# Qwiic-OpenLog.net
KiCad netlist of a schematic drawn in EAGLE
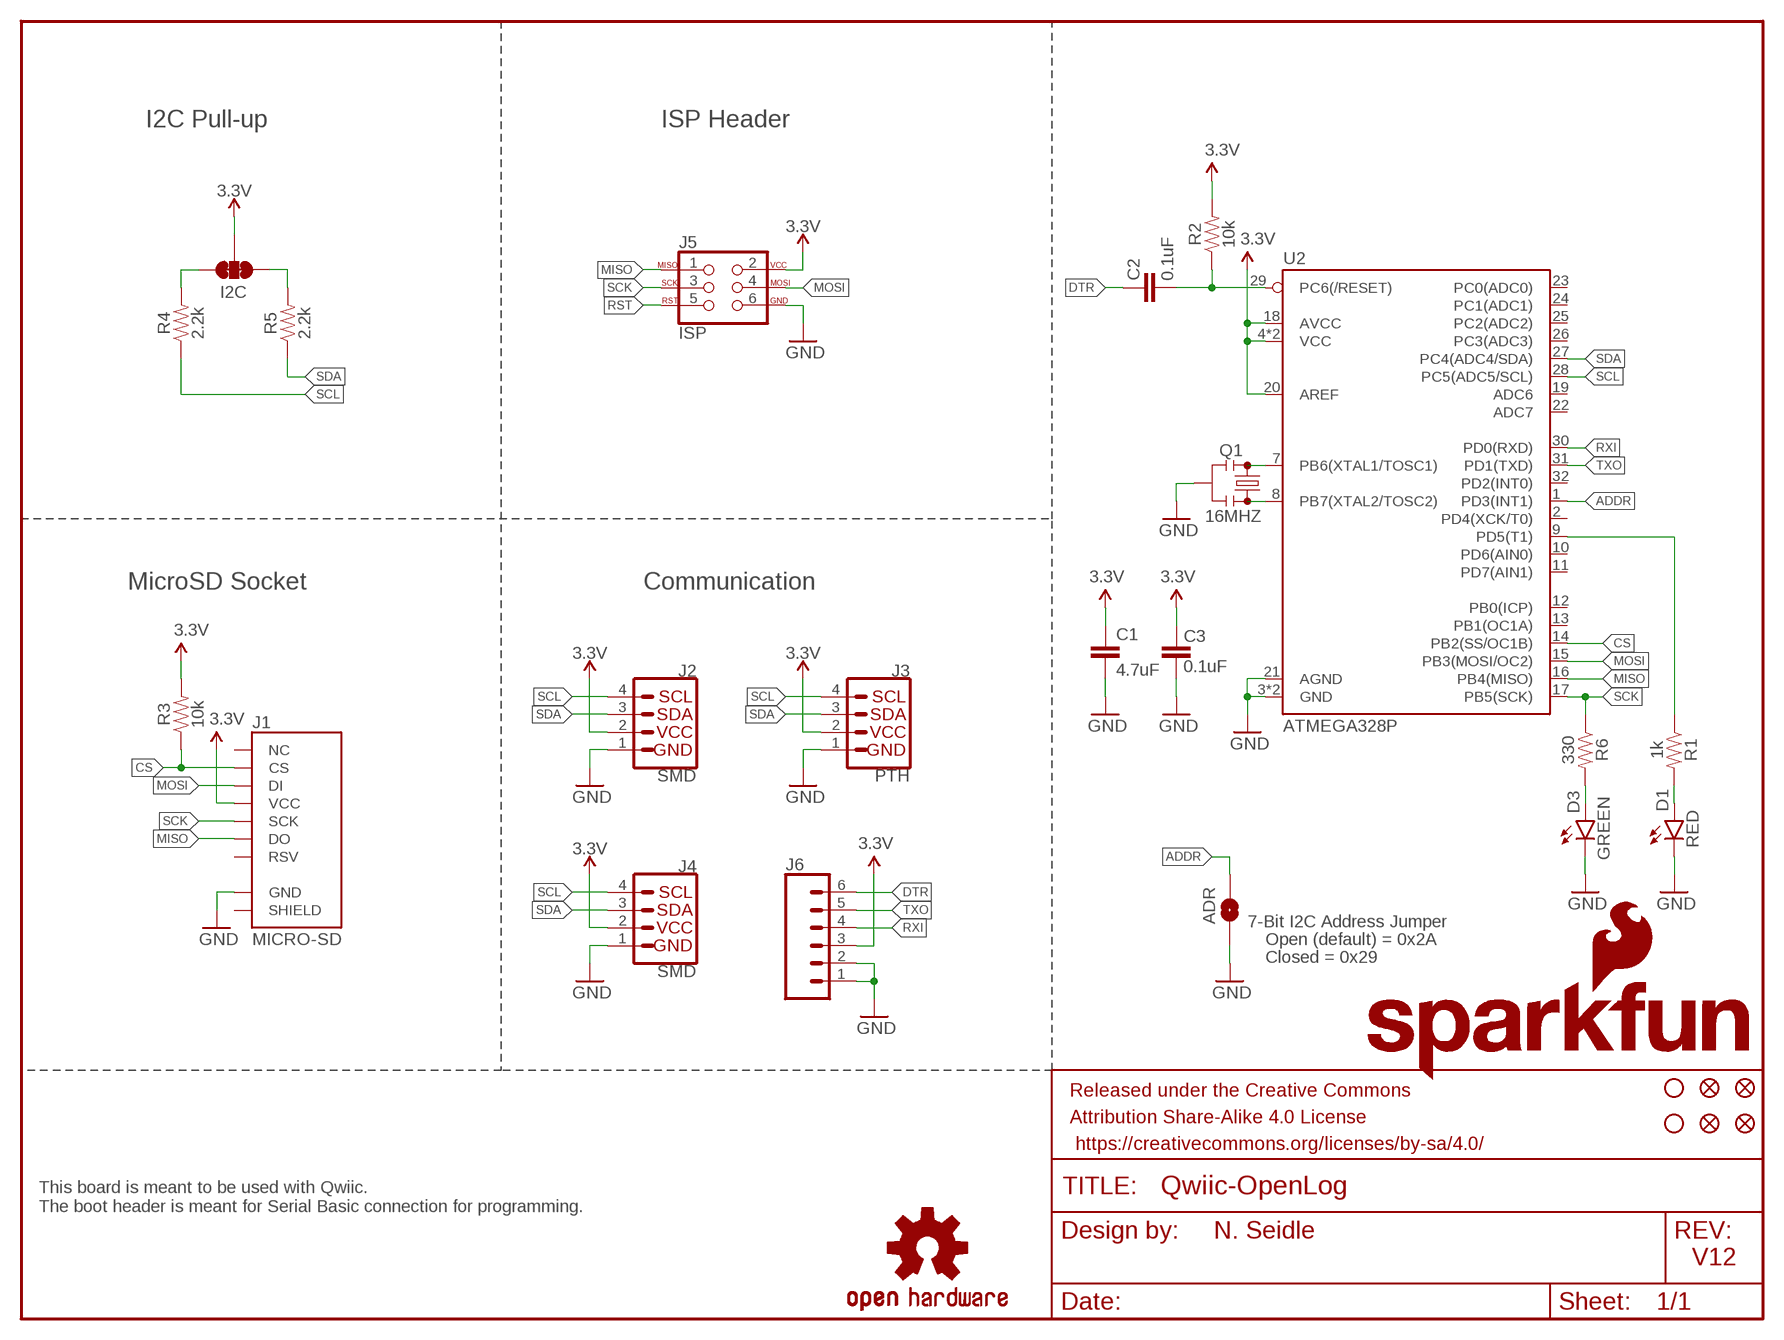
[diagram p0: schematic, sheet 1]

(export (version "E")
  (design (tool "Eeschema 10.0.6"))
  (components
    (comp (ref "ADR")
      (value "SOLDERJUMPERNO")
      (footprint "eagle-import:SJ_2S-NO")
      (libsource (lib "eagle-import") (part "SOLDERJUMPERNO"))
    )
    (comp (ref "C1")
      (value "4.7uF")
      (footprint "eagle-import:0603")
      (libsource (lib "eagle-import") (part "4.7UF-0603-6.3V-(10%)"))
    )
    (comp (ref "C2")
      (value "0.1uF")
      (footprint "eagle-import:0603")
      (libsource (lib "eagle-import") (part "0.1UF-0603-25V-(+80/-20%)"))
    )
    (comp (ref "C3")
      (value "0.1uF")
      (footprint "eagle-import:0603")
      (libsource (lib "eagle-import") (part "0.1UF-0603-25V-(+80/-20%)"))
    )
    (comp (ref "D1")
      (value "RED")
      (footprint "eagle-import:LED-0603")
      (libsource (lib "eagle-import") (part "LED-RED0603"))
    )
    (comp (ref "D3")
      (value "GREEN")
      (footprint "eagle-import:LED-0603")
      (libsource (lib "eagle-import") (part "LED-GREEN0603"))
    )
    (comp (ref "FID1")
      (value "FIDUCIALUFIDUCIAL")
      (footprint "eagle-import:FIDUCIAL-MICRO")
      (libsource (lib "eagle-import") (part "FIDUCIALUFIDUCIAL"))
    )
    (comp (ref "FID2")
      (value "FIDUCIALUFIDUCIAL")
      (footprint "eagle-import:FIDUCIAL-MICRO")
      (libsource (lib "eagle-import") (part "FIDUCIALUFIDUCIAL"))
    )
    (comp (ref "FID3")
      (value "FIDUCIALUFIDUCIAL")
      (footprint "eagle-import:FIDUCIAL-MICRO")
      (libsource (lib "eagle-import") (part "FIDUCIALUFIDUCIAL"))
    )
    (comp (ref "FID4")
      (value "FIDUCIALUFIDUCIAL")
      (footprint "eagle-import:FIDUCIAL-MICRO")
      (libsource (lib "eagle-import") (part "FIDUCIALUFIDUCIAL"))
    )
    (comp (ref "FRAME1")
      (value "FRAME-LETTER")
      (footprint "eagle-import:CREATIVE_COMMONS")
      (libsource (lib "eagle-import") (part "FRAME-LETTER"))
    )
    (comp (ref "I2C")
      (value "JUMPER-SMT_3_2-NC_TRACE_SILK")
      (footprint "eagle-import:SMT-JUMPER_3_2-NC_TRACE_SILK")
      (libsource (lib "eagle-import") (part "JUMPER-SMT_3_2-NC_TRACE_SILK"))
    )
    (comp (ref "J1")
      (value "MICRO-SD")
      (footprint "eagle-import:MICRO-SD-SOCKET")
      (libsource (lib "eagle-import") (part "MICRO-SD_CARD_SOCKETPUSH-PUSH"))
    )
    (comp (ref "J2")
      (value "SMD")
      (footprint "eagle-import:1X04_1MM_RA")
      (libsource (lib "eagle-import") (part "QWIIC_CONNECTORJS-1MM"))
    )
    (comp (ref "J3")
      (value "PTH")
      (footprint "eagle-import:1X04_NO_SILK")
      (libsource (lib "eagle-import") (part "I2C_STANDARD_NO_SILK"))
    )
    (comp (ref "J4")
      (value "SMD")
      (footprint "eagle-import:1X04_1MM_RA")
      (libsource (lib "eagle-import") (part "QWIIC_CONNECTORJS-1MM"))
    )
    (comp (ref "J5")
      (value "ISP")
      (footprint "eagle-import:2X3_TEST_POINTS")
      (libsource (lib "eagle-import") (part "AVR_SPI_PROG_3X2TESTPOINTS"))
    )
    (comp (ref "J6")
      (value "CONN_06NO_SILK_NO_POP")
      (footprint "eagle-import:1X06_NO_SILK")
      (libsource (lib "eagle-import") (part "CONN_06NO_SILK_NO_POP"))
    )
    (comp (ref "JP3")
      (value "STAND-OFF")
      (footprint "eagle-import:STAND-OFF")
      (libsource (lib "eagle-import") (part "STAND-OFF"))
    )
    (comp (ref "JP4")
      (value "STAND-OFF")
      (footprint "eagle-import:STAND-OFF")
      (libsource (lib "eagle-import") (part "STAND-OFF"))
    )
    (comp (ref "LOGO1")
      (value "SFE_LOGO_FLAME.1_INCH")
      (footprint "eagle-import:SFE_LOGO_FLAME_.1")
      (libsource (lib "eagle-import") (part "SFE_LOGO_FLAME.1_INCH"))
    )
    (comp (ref "LOGO2")
      (value "OSHW-LOGOMINI")
      (footprint "eagle-import:OSHW-LOGO-MINI")
      (libsource (lib "eagle-import") (part "OSHW-LOGOMINI"))
    )
    (comp (ref "LOGO4")
      (value "SFE_LOGO_NAME_FLAME.1_INCH")
      (footprint "eagle-import:SFE_LOGO_NAME_FLAME_.1")
      (libsource (lib "eagle-import") (part "SFE_LOGO_NAME_FLAME.1_INCH"))
    )
    (comp (ref "Q1")
      (value "16MHZ")
      (footprint "eagle-import:RESONATOR-SMD")
      (libsource (lib "eagle-import") (part "RESONATOR16MHZ"))
    )
    (comp (ref "R1")
      (value "1k")
      (footprint "eagle-import:0603")
      (libsource (lib "eagle-import") (part "1KOHM-0603-1/10W-1%"))
    )
    (comp (ref "R2")
      (value "10k")
      (footprint "eagle-import:0603")
      (libsource (lib "eagle-import") (part "10KOHM-0603-1/10W-1%"))
    )
    (comp (ref "R3")
      (value "10k")
      (footprint "eagle-import:0603")
      (libsource (lib "eagle-import") (part "10KOHM-0603-1/10W-1%"))
    )
    (comp (ref "R4")
      (value "2.2k")
      (footprint "eagle-import:0603")
      (libsource (lib "eagle-import") (part "2.2KOHM-0603-1/10W-1%"))
    )
    (comp (ref "R5")
      (value "2.2k")
      (footprint "eagle-import:0603")
      (libsource (lib "eagle-import") (part "2.2KOHM-0603-1/10W-1%"))
    )
    (comp (ref "R6")
      (value "330")
      (footprint "eagle-import:0603")
      (libsource (lib "eagle-import") (part "330OHM-0603-1/10W-1%"))
    )
    (comp (ref "U2")
      (value "ATMEGA328P")
      (footprint "eagle-import:TQFP32-08")
      (libsource (lib "eagle-import") (part "ATMEGA328P_TQFP"))
    )
  )
  (nets
    (net (code "1") (name "3.3V") (class "Default")
      (node (ref "C1") (pin "1") (pinfunction "1_1") (pintype "passive"))
      (node (ref "C3") (pin "2") (pinfunction "2_2") (pintype "passive"))
      (node (ref "I2C") (pin "2") (pinfunction "2_2") (pintype "passive"))
      (node (ref "J1") (pin "VCC") (pinfunction "VCC_VCC") (pintype "bidirectional"))
      (node (ref "J2") (pin "2") (pinfunction "2_2") (pintype "power_in"))
      (node (ref "J3") (pin "2") (pinfunction "VCC_2") (pintype "power_in"))
      (node (ref "J4") (pin "2") (pinfunction "2_2") (pintype "power_in"))
      (node (ref "J5") (pin "2") (pinfunction "2_2") (pintype "passive"))
      (node (ref "J6") (pin "3") (pinfunction "3_3") (pintype "passive"))
      (node (ref "R2") (pin "2") (pinfunction "2_2") (pintype "passive"))
      (node (ref "R3") (pin "2") (pinfunction "2_2") (pintype "passive"))
      (node (ref "U2") (pin "18") (pinfunction "AVCC_18") (pintype "bidirectional"))
      (node (ref "U2") (pin "20") (pinfunction "AREF_20") (pintype "bidirectional"))
      (node (ref "U2") (pin "4") (pinfunction "VCC_4") (pintype "bidirectional"))
      (node (ref "U2") (pin "6") (pinfunction "VCC_6") (pintype "bidirectional"))
    )
    (net (code "2") (name "ADDR") (class "Default")
      (node (ref "ADR") (pin "2") (pinfunction "2_2") (pintype "passive"))
      (node (ref "U2") (pin "1") (pinfunction "PD3(INT1)_1") (pintype "bidirectional"))
    )
    (net (code "3") (name "CS") (class "Default")
      (node (ref "J1") (pin "CS") (pinfunction "CS_CS") (pintype "bidirectional"))
      (node (ref "R3") (pin "1") (pinfunction "1_1") (pintype "passive"))
      (node (ref "U2") (pin "14") (pinfunction "PB2(SS/OC1B)_14") (pintype "bidirectional"))
    )
    (net (code "4") (name "DTR") (class "Default")
      (node (ref "C2") (pin "2") (pinfunction "2_2") (pintype "passive"))
      (node (ref "J6") (pin "6") (pinfunction "6_6") (pintype "passive"))
    )
    (net (code "5") (name "GND") (class "Default")
      (node (ref "ADR") (pin "1") (pinfunction "1_1") (pintype "passive"))
      (node (ref "C1") (pin "2") (pinfunction "2_2") (pintype "passive"))
      (node (ref "C3") (pin "1") (pinfunction "1_1") (pintype "passive"))
      (node (ref "D1") (pin "C") (pinfunction "C_C") (pintype "passive"))
      (node (ref "D3") (pin "C") (pinfunction "C_C") (pintype "passive"))
      (node (ref "J1") (pin "GND") (pinfunction "GND_GND") (pintype "bidirectional"))
      (node (ref "J2") (pin "1") (pinfunction "1_1") (pintype "power_in"))
      (node (ref "J3") (pin "1") (pinfunction "GND_1") (pintype "power_in"))
      (node (ref "J4") (pin "1") (pinfunction "1_1") (pintype "power_in"))
      (node (ref "J5") (pin "6") (pinfunction "6_6") (pintype "passive"))
      (node (ref "J6") (pin "1") (pinfunction "1_1") (pintype "passive"))
      (node (ref "J6") (pin "2") (pinfunction "2_2") (pintype "passive"))
      (node (ref "Q1") (pin "2") (pinfunction "2_2") (pintype "passive"))
      (node (ref "U2") (pin "21") (pinfunction "AGND_21") (pintype "bidirectional"))
      (node (ref "U2") (pin "3") (pinfunction "GND_3") (pintype "bidirectional"))
      (node (ref "U2") (pin "5") (pinfunction "GND_5") (pintype "bidirectional"))
    )
    (net (code "6") (name "MISO") (class "Default")
      (node (ref "J1") (pin "DO") (pinfunction "DO_DO") (pintype "bidirectional"))
      (node (ref "J5") (pin "1") (pinfunction "1_1") (pintype "passive"))
      (node (ref "U2") (pin "16") (pinfunction "PB4(MISO)_16") (pintype "bidirectional"))
    )
    (net (code "7") (name "MOSI") (class "Default")
      (node (ref "J1") (pin "DI") (pinfunction "DI_DI") (pintype "bidirectional"))
      (node (ref "J5") (pin "4") (pinfunction "4_4") (pintype "passive"))
      (node (ref "U2") (pin "15") (pinfunction "PB3(MOSI/OC2)_15") (pintype "bidirectional"))
    )
    (net (code "8") (name "Net-(D1-PadA)") (class "Default")
      (node (ref "D1") (pin "A") (pinfunction "A_A") (pintype "passive"))
      (node (ref "R1") (pin "2") (pinfunction "2_2") (pintype "passive"))
    )
    (net (code "9") (name "Net-(D3-PadA)") (class "Default")
      (node (ref "D3") (pin "A") (pinfunction "A_A") (pintype "passive"))
      (node (ref "R6") (pin "2") (pinfunction "2_2") (pintype "passive"))
    )
    (net (code "10") (name "Net-(I2C-Pad1)") (class "Default")
      (node (ref "I2C") (pin "1") (pinfunction "1_1") (pintype "passive"))
      (node (ref "R5") (pin "2") (pinfunction "2_2") (pintype "passive"))
    )
    (net (code "11") (name "Net-(I2C-Pad3)") (class "Default")
      (node (ref "I2C") (pin "3") (pinfunction "3_3") (pintype "passive"))
      (node (ref "R4") (pin "2") (pinfunction "2_2") (pintype "passive"))
    )
    (net (code "12") (name "Net-(U2-PB6(XTAL1{slash}TOSC1))") (class "Default")
      (node (ref "Q1") (pin "3") (pinfunction "3_3") (pintype "passive"))
      (node (ref "U2") (pin "7") (pinfunction "PB6(XTAL1/TOSC1)_7") (pintype "bidirectional"))
    )
    (net (code "13") (name "Net-(U2-PB7(XTAL2{slash}TOSC2))") (class "Default")
      (node (ref "Q1") (pin "1") (pinfunction "1_1") (pintype "passive"))
      (node (ref "U2") (pin "8") (pinfunction "PB7(XTAL2/TOSC2)_8") (pintype "bidirectional"))
    )
    (net (code "14") (name "Net-(U2-PD5(T1))") (class "Default")
      (node (ref "R1") (pin "1") (pinfunction "1_1") (pintype "passive"))
      (node (ref "U2") (pin "9") (pinfunction "PD5(T1)_9") (pintype "bidirectional"))
    )
    (net (code "15") (name "RST") (class "Default")
      (node (ref "C2") (pin "1") (pinfunction "1_1") (pintype "passive"))
      (node (ref "J5") (pin "5") (pinfunction "5_5") (pintype "passive"))
      (node (ref "R2") (pin "1") (pinfunction "1_1") (pintype "passive"))
      (node (ref "U2") (pin "29") (pinfunction "PC6(/RESET)_29") (pintype "bidirectional"))
    )
    (net (code "16") (name "RXI") (class "Default")
      (node (ref "J6") (pin "4") (pinfunction "4_4") (pintype "passive"))
      (node (ref "U2") (pin "30") (pinfunction "PD0(RXD)_30") (pintype "bidirectional"))
    )
    (net (code "17") (name "SCK") (class "Default")
      (node (ref "J1") (pin "SCLK") (pinfunction "SCK_SCLK") (pintype "bidirectional"))
      (node (ref "J5") (pin "3") (pinfunction "3_3") (pintype "passive"))
      (node (ref "R6") (pin "1") (pinfunction "1_1") (pintype "passive"))
      (node (ref "U2") (pin "17") (pinfunction "PB5(SCK)_17") (pintype "bidirectional"))
    )
    (net (code "18") (name "SCL") (class "Default")
      (node (ref "J2") (pin "4") (pinfunction "4_4") (pintype "passive"))
      (node (ref "J3") (pin "4") (pinfunction "SCL_4") (pintype "passive"))
      (node (ref "J4") (pin "4") (pinfunction "4_4") (pintype "passive"))
      (node (ref "R4") (pin "1") (pinfunction "1_1") (pintype "passive"))
      (node (ref "U2") (pin "28") (pinfunction "PC5(ADC5/SCL)_28") (pintype "bidirectional"))
    )
    (net (code "19") (name "SDA") (class "Default")
      (node (ref "J2") (pin "3") (pinfunction "3_3") (pintype "passive"))
      (node (ref "J3") (pin "3") (pinfunction "SDA_3") (pintype "passive"))
      (node (ref "J4") (pin "3") (pinfunction "3_3") (pintype "passive"))
      (node (ref "R5") (pin "1") (pinfunction "1_1") (pintype "passive"))
      (node (ref "U2") (pin "27") (pinfunction "PC4(ADC4/SDA)_27") (pintype "bidirectional"))
    )
    (net (code "20") (name "TXO") (class "Default")
      (node (ref "J6") (pin "5") (pinfunction "5_5") (pintype "passive"))
      (node (ref "U2") (pin "31") (pinfunction "PD1(TXD)_31") (pintype "bidirectional"))
    )
    (net (code "21") (name "unconnected-(J1-NC-PadRSV2)") (class "Default")
      (node (ref "J1") (pin "RSV2") (pinfunction "NC_RSV2") (pintype "bidirectional"))
    )
    (net (code "22") (name "unconnected-(J1-RSV-PadRSV1)") (class "Default")
      (node (ref "J1") (pin "RSV1") (pinfunction "RSV_RSV1") (pintype "bidirectional"))
    )
    (net (code "23") (name "unconnected-(J1-SHIELD-PadCD1)") (class "Default")
      (node (ref "J1") (pin "CD1") (pinfunction "SHIELD_CD1") (pintype "bidirectional"))
    )
    (net (code "24") (name "unconnected-(U2-ADC6-Pad19)") (class "Default")
      (node (ref "U2") (pin "19") (pinfunction "ADC6_19") (pintype "bidirectional"))
    )
    (net (code "25") (name "unconnected-(U2-ADC7-Pad22)") (class "Default")
      (node (ref "U2") (pin "22") (pinfunction "ADC7_22") (pintype "bidirectional"))
    )
    (net (code "26") (name "unconnected-(U2-PB0(ICP)-Pad12)") (class "Default")
      (node (ref "U2") (pin "12") (pinfunction "PB0(ICP)_12") (pintype "bidirectional"))
    )
    (net (code "27") (name "unconnected-(U2-PB1(OC1A)-Pad13)") (class "Default")
      (node (ref "U2") (pin "13") (pinfunction "PB1(OC1A)_13") (pintype "bidirectional"))
    )
    (net (code "28") (name "unconnected-(U2-PC0(ADC0)-Pad23)") (class "Default")
      (node (ref "U2") (pin "23") (pinfunction "PC0(ADC0)_23") (pintype "bidirectional"))
    )
    (net (code "29") (name "unconnected-(U2-PC1(ADC1)-Pad24)") (class "Default")
      (node (ref "U2") (pin "24") (pinfunction "PC1(ADC1)_24") (pintype "bidirectional"))
    )
    (net (code "30") (name "unconnected-(U2-PC2(ADC2)-Pad25)") (class "Default")
      (node (ref "U2") (pin "25") (pinfunction "PC2(ADC2)_25") (pintype "bidirectional"))
    )
    (net (code "31") (name "unconnected-(U2-PC3(ADC3)-Pad26)") (class "Default")
      (node (ref "U2") (pin "26") (pinfunction "PC3(ADC3)_26") (pintype "bidirectional"))
    )
    (net (code "32") (name "unconnected-(U2-PD2(INT0)-Pad32)") (class "Default")
      (node (ref "U2") (pin "32") (pinfunction "PD2(INT0)_32") (pintype "bidirectional"))
    )
    (net (code "33") (name "unconnected-(U2-PD4(XCK{slash}T0)-Pad2)") (class "Default")
      (node (ref "U2") (pin "2") (pinfunction "PD4(XCK/T0)_2") (pintype "bidirectional"))
    )
    (net (code "34") (name "unconnected-(U2-PD6(AIN0)-Pad10)") (class "Default")
      (node (ref "U2") (pin "10") (pinfunction "PD6(AIN0)_10") (pintype "bidirectional"))
    )
    (net (code "35") (name "unconnected-(U2-PD7(AIN1)-Pad11)") (class "Default")
      (node (ref "U2") (pin "11") (pinfunction "PD7(AIN1)_11") (pintype "bidirectional"))
    )
  )
)
